# shift.net
KiCad netlist of a schematic drawn in EAGLE
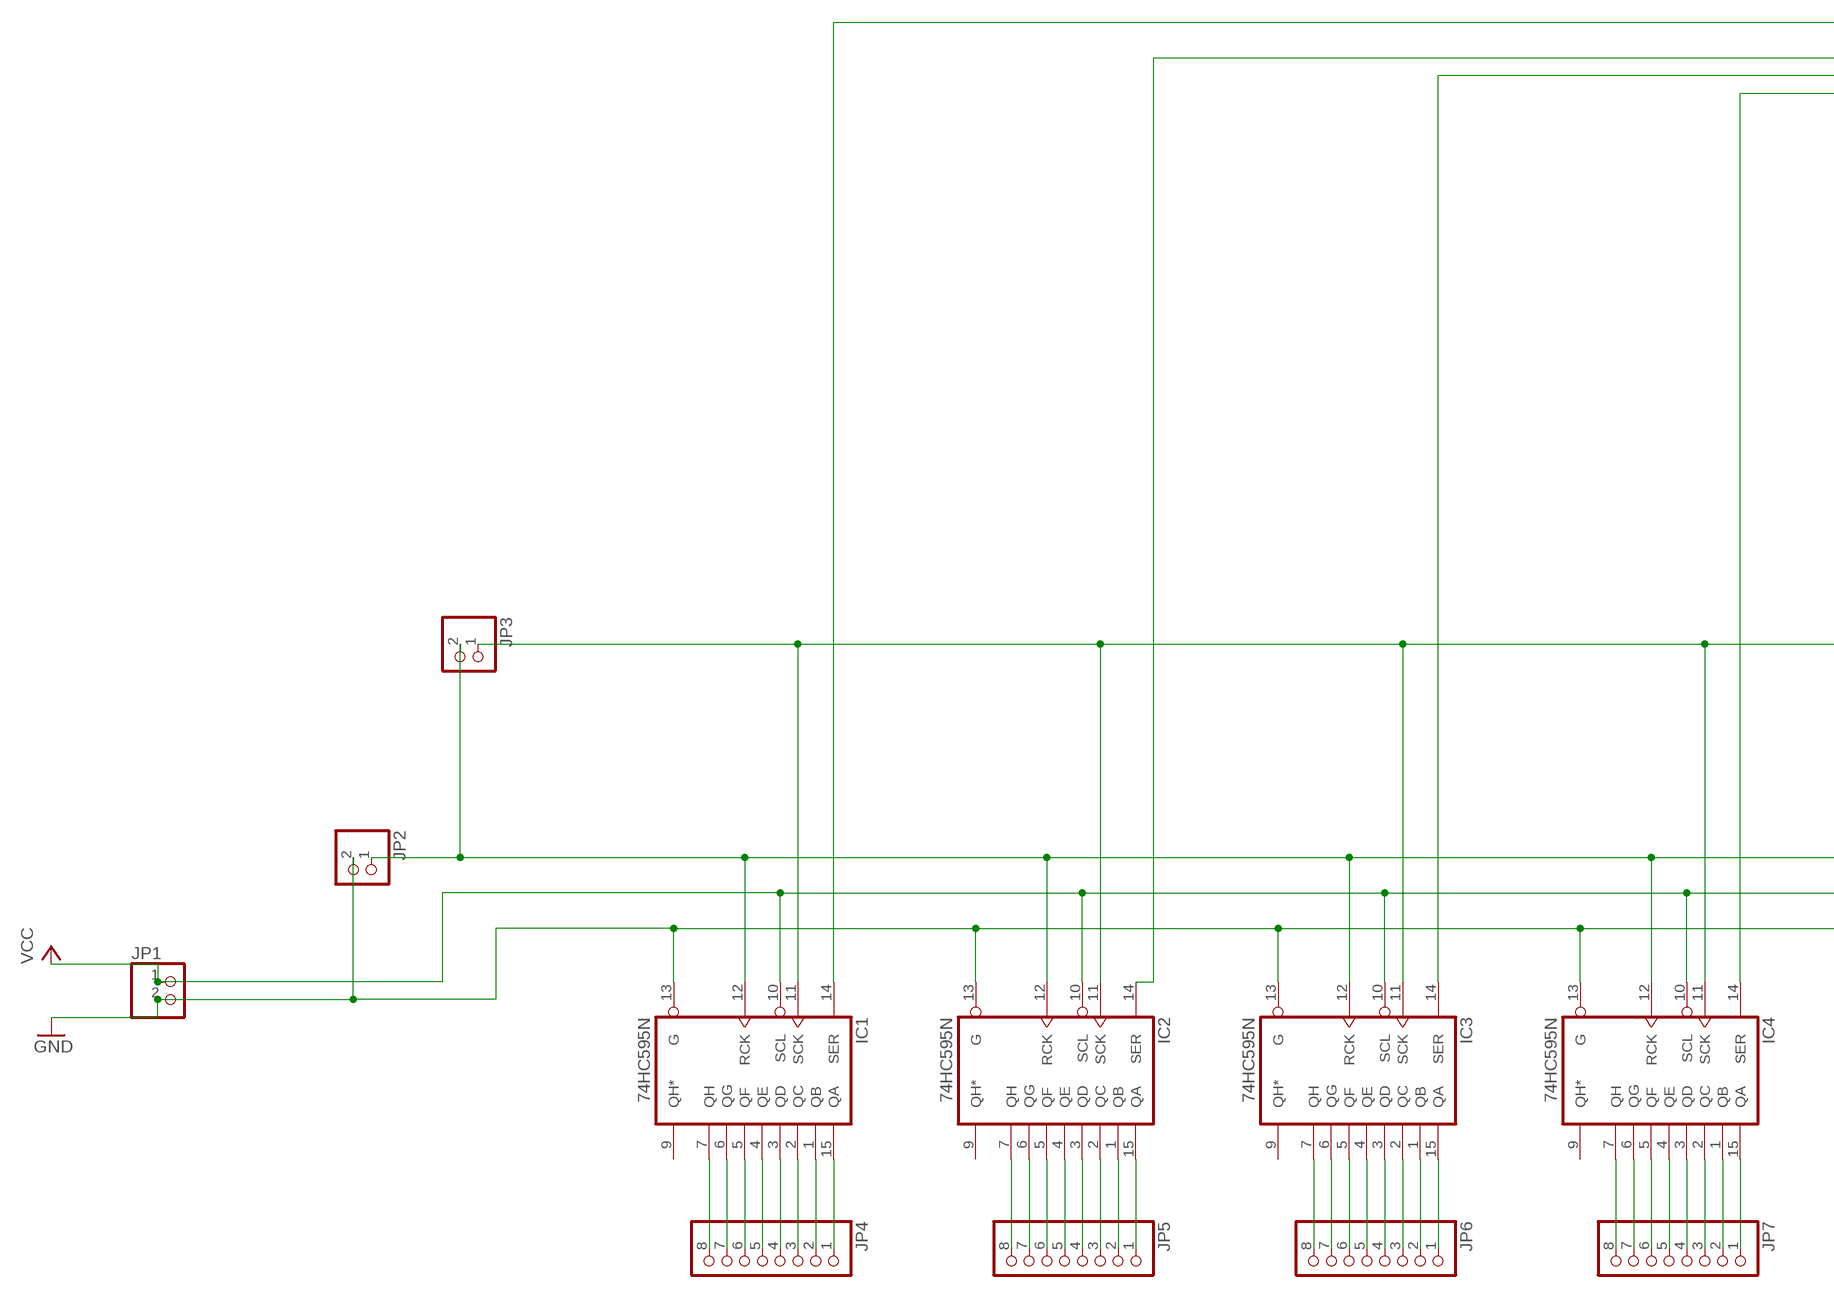
[diagram p0: schematic, sheet 1, part 1 of 2]
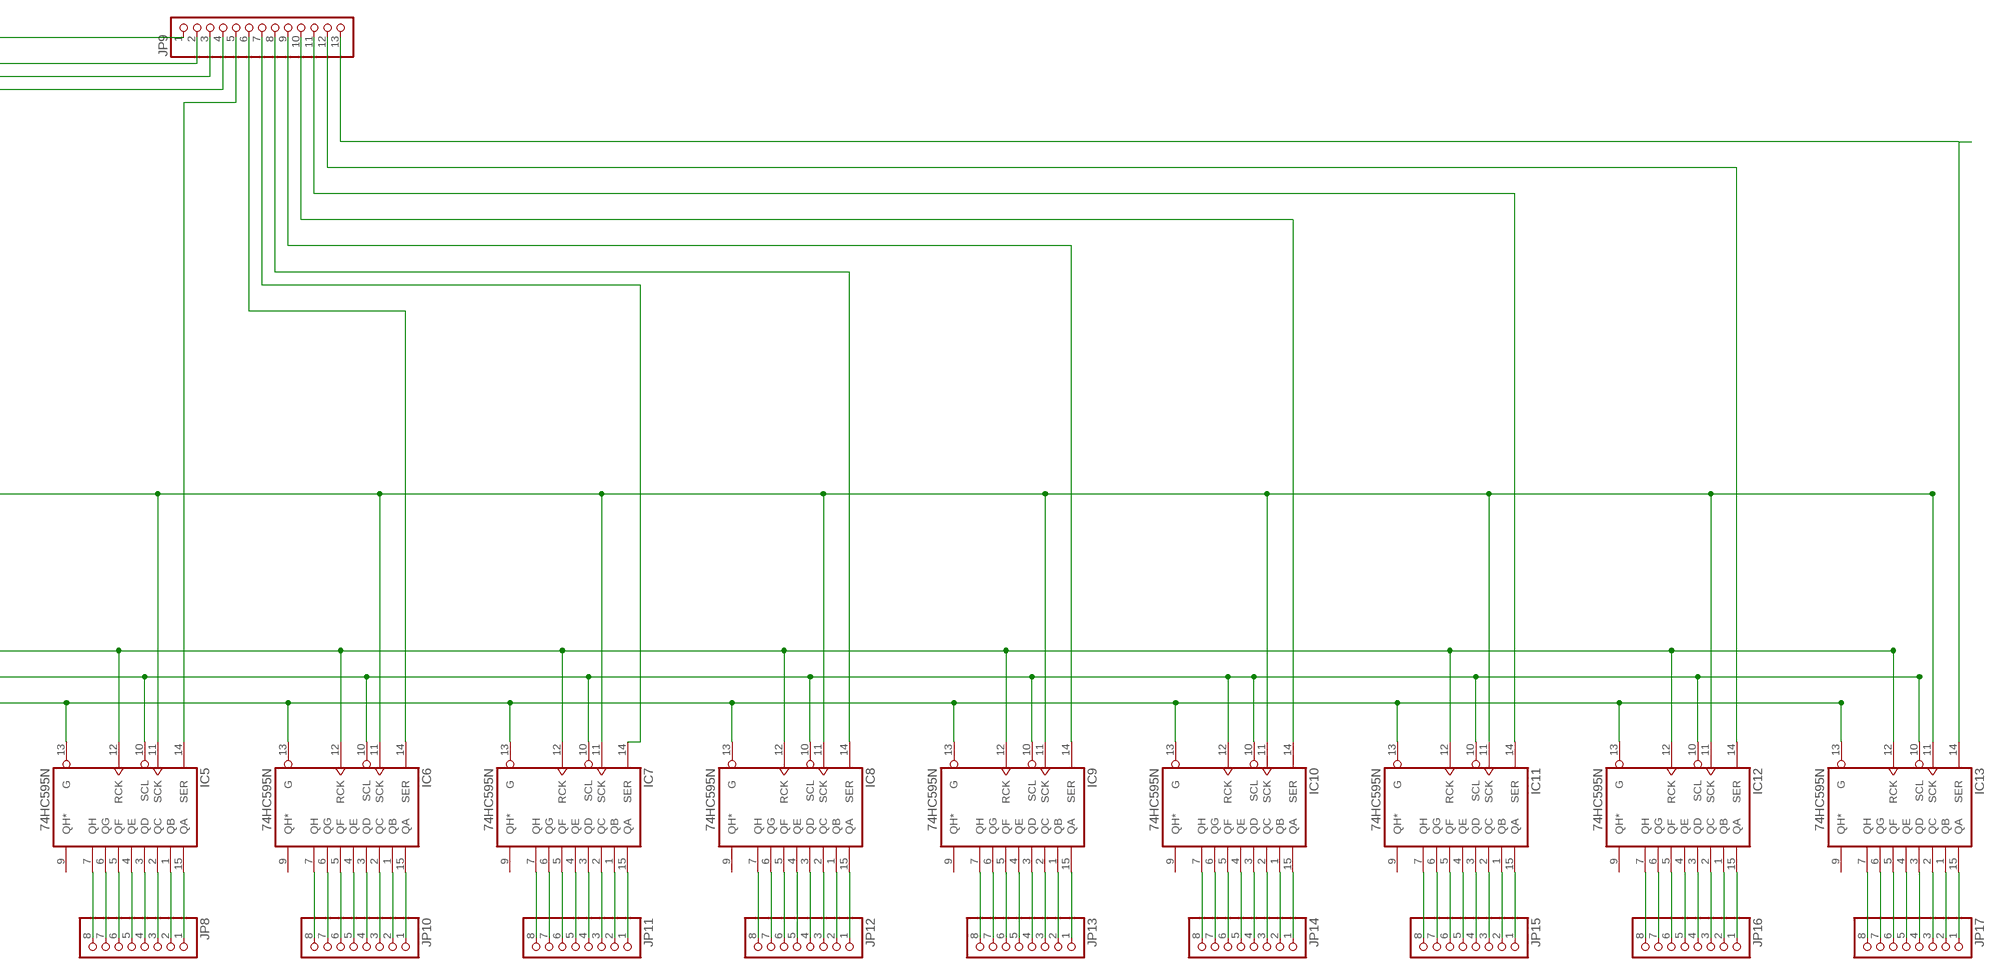
[diagram p1: schematic, sheet 1, part 2 of 2]

(export (version "E")
  (design (tool "Eeschema 10.0.6"))
  (components
    (comp (ref "IC1")
      (value "74HC595N")
      (footprint "eagle-import:DIL16")
      (libsource (lib "eagle-import") (part "74595NHC"))
    )
    (comp (ref "IC2")
      (value "74HC595N")
      (footprint "eagle-import:DIL16")
      (libsource (lib "eagle-import") (part "74595NHC"))
    )
    (comp (ref "IC3")
      (value "74HC595N")
      (footprint "eagle-import:DIL16")
      (libsource (lib "eagle-import") (part "74595NHC"))
    )
    (comp (ref "IC4")
      (value "74HC595N")
      (footprint "eagle-import:DIL16")
      (libsource (lib "eagle-import") (part "74595NHC"))
    )
    (comp (ref "IC5")
      (value "74HC595N")
      (footprint "eagle-import:DIL16")
      (libsource (lib "eagle-import") (part "74595NHC"))
    )
    (comp (ref "IC6")
      (value "74HC595N")
      (footprint "eagle-import:DIL16")
      (libsource (lib "eagle-import") (part "74595NHC"))
    )
    (comp (ref "IC7")
      (value "74HC595N")
      (footprint "eagle-import:DIL16")
      (libsource (lib "eagle-import") (part "74595NHC"))
    )
    (comp (ref "IC8")
      (value "74HC595N")
      (footprint "eagle-import:DIL16")
      (libsource (lib "eagle-import") (part "74595NHC"))
    )
    (comp (ref "IC9")
      (value "74HC595N")
      (footprint "eagle-import:DIL16")
      (libsource (lib "eagle-import") (part "74595NHC"))
    )
    (comp (ref "IC10")
      (value "74HC595N")
      (footprint "eagle-import:DIL16")
      (libsource (lib "eagle-import") (part "74595NHC"))
    )
    (comp (ref "IC11")
      (value "74HC595N")
      (footprint "eagle-import:DIL16")
      (libsource (lib "eagle-import") (part "74595NHC"))
    )
    (comp (ref "IC12")
      (value "74HC595N")
      (footprint "eagle-import:DIL16")
      (libsource (lib "eagle-import") (part "74595NHC"))
    )
    (comp (ref "IC13")
      (value "74HC595N")
      (footprint "eagle-import:DIL16")
      (libsource (lib "eagle-import") (part "74595NHC"))
    )
    (comp (ref "JP1")
      (value "PINHD-1X2")
      (footprint "eagle-import:1X02")
      (libsource (lib "eagle-import") (part "PINHD-1X2"))
    )
    (comp (ref "JP2")
      (value "PINHD-1X2")
      (footprint "eagle-import:1X02")
      (libsource (lib "eagle-import") (part "PINHD-1X2"))
    )
    (comp (ref "JP3")
      (value "PINHD-1X2")
      (footprint "eagle-import:1X02")
      (libsource (lib "eagle-import") (part "PINHD-1X2"))
    )
    (comp (ref "JP4")
      (value "PINHD-1X8")
      (footprint "eagle-import:1X08")
      (libsource (lib "eagle-import") (part "PINHD-1X8"))
    )
    (comp (ref "JP5")
      (value "PINHD-1X8")
      (footprint "eagle-import:1X08")
      (libsource (lib "eagle-import") (part "PINHD-1X8"))
    )
    (comp (ref "JP6")
      (value "PINHD-1X8")
      (footprint "eagle-import:1X08")
      (libsource (lib "eagle-import") (part "PINHD-1X8"))
    )
    (comp (ref "JP7")
      (value "PINHD-1X8")
      (footprint "eagle-import:1X08")
      (libsource (lib "eagle-import") (part "PINHD-1X8"))
    )
    (comp (ref "JP8")
      (value "PINHD-1X8")
      (footprint "eagle-import:1X08")
      (libsource (lib "eagle-import") (part "PINHD-1X8"))
    )
    (comp (ref "JP9")
      (value "PINHD-1X13")
      (footprint "eagle-import:1X13")
      (libsource (lib "eagle-import") (part "PINHD-1X13"))
    )
    (comp (ref "JP10")
      (value "PINHD-1X8")
      (footprint "eagle-import:1X08")
      (libsource (lib "eagle-import") (part "PINHD-1X8"))
    )
    (comp (ref "JP11")
      (value "PINHD-1X8")
      (footprint "eagle-import:1X08")
      (libsource (lib "eagle-import") (part "PINHD-1X8"))
    )
    (comp (ref "JP12")
      (value "PINHD-1X8")
      (footprint "eagle-import:1X08")
      (libsource (lib "eagle-import") (part "PINHD-1X8"))
    )
    (comp (ref "JP13")
      (value "PINHD-1X8")
      (footprint "eagle-import:1X08")
      (libsource (lib "eagle-import") (part "PINHD-1X8"))
    )
    (comp (ref "JP14")
      (value "PINHD-1X8")
      (footprint "eagle-import:1X08")
      (libsource (lib "eagle-import") (part "PINHD-1X8"))
    )
    (comp (ref "JP15")
      (value "PINHD-1X8")
      (footprint "eagle-import:1X08")
      (libsource (lib "eagle-import") (part "PINHD-1X8"))
    )
    (comp (ref "JP16")
      (value "PINHD-1X8")
      (footprint "eagle-import:1X08")
      (libsource (lib "eagle-import") (part "PINHD-1X8"))
    )
    (comp (ref "JP17")
      (value "PINHD-1X8")
      (footprint "eagle-import:1X08")
      (libsource (lib "eagle-import") (part "PINHD-1X8"))
    )
  )
  (nets
    (net (code "1") (name "GND") (class "Default")
      (node (ref "IC1") (pin "13") (pinfunction "G_13") (pintype "input"))
      (node (ref "IC10") (pin "13") (pinfunction "G_13") (pintype "input"))
      (node (ref "IC11") (pin "13") (pinfunction "G_13") (pintype "input"))
      (node (ref "IC12") (pin "13") (pinfunction "G_13") (pintype "input"))
      (node (ref "IC13") (pin "13") (pinfunction "G_13") (pintype "input"))
      (node (ref "IC2") (pin "13") (pinfunction "G_13") (pintype "input"))
      (node (ref "IC3") (pin "13") (pinfunction "G_13") (pintype "input"))
      (node (ref "IC4") (pin "13") (pinfunction "G_13") (pintype "input"))
      (node (ref "IC5") (pin "13") (pinfunction "G_13") (pintype "input"))
      (node (ref "IC6") (pin "13") (pinfunction "G_13") (pintype "input"))
      (node (ref "IC7") (pin "13") (pinfunction "G_13") (pintype "input"))
      (node (ref "IC8") (pin "13") (pinfunction "G_13") (pintype "input"))
      (node (ref "IC9") (pin "13") (pinfunction "G_13") (pintype "input"))
      (node (ref "JP1") (pin "2") (pinfunction "2_2") (pintype "passive"))
      (node (ref "JP2") (pin "2") (pinfunction "2_2") (pintype "passive"))
    )
    (net (code "2") (name "Net-(IC1A-QA)") (class "Default")
      (node (ref "IC1") (pin "15") (pinfunction "QA_15") (pintype "tri_state"))
      (node (ref "JP4") (pin "1") (pinfunction "1_1") (pintype "passive"))
    )
    (net (code "3") (name "Net-(IC1A-QB)") (class "Default")
      (node (ref "IC1") (pin "1") (pinfunction "QB_1") (pintype "tri_state"))
      (node (ref "JP4") (pin "2") (pinfunction "2_2") (pintype "passive"))
    )
    (net (code "4") (name "Net-(IC1A-QC)") (class "Default")
      (node (ref "IC1") (pin "2") (pinfunction "QC_2") (pintype "tri_state"))
      (node (ref "JP4") (pin "3") (pinfunction "3_3") (pintype "passive"))
    )
    (net (code "5") (name "Net-(IC1A-QD)") (class "Default")
      (node (ref "IC1") (pin "3") (pinfunction "QD_3") (pintype "tri_state"))
      (node (ref "JP4") (pin "4") (pinfunction "4_4") (pintype "passive"))
    )
    (net (code "6") (name "Net-(IC1A-QE)") (class "Default")
      (node (ref "IC1") (pin "4") (pinfunction "QE_4") (pintype "tri_state"))
      (node (ref "JP4") (pin "5") (pinfunction "5_5") (pintype "passive"))
    )
    (net (code "7") (name "Net-(IC1A-QF)") (class "Default")
      (node (ref "IC1") (pin "5") (pinfunction "QF_5") (pintype "tri_state"))
      (node (ref "JP4") (pin "6") (pinfunction "6_6") (pintype "passive"))
    )
    (net (code "8") (name "Net-(IC1A-QG)") (class "Default")
      (node (ref "IC1") (pin "6") (pinfunction "QG_6") (pintype "tri_state"))
      (node (ref "JP4") (pin "7") (pinfunction "7_7") (pintype "passive"))
    )
    (net (code "9") (name "Net-(IC1A-QH)") (class "Default")
      (node (ref "IC1") (pin "7") (pinfunction "QH_7") (pintype "tri_state"))
      (node (ref "JP4") (pin "8") (pinfunction "8_8") (pintype "passive"))
    )
    (net (code "10") (name "Net-(IC1A-SER)") (class "Default")
      (node (ref "IC1") (pin "14") (pinfunction "SER_14") (pintype "input"))
      (node (ref "JP9") (pin "1") (pinfunction "1_1") (pintype "passive"))
    )
    (net (code "11") (name "Net-(IC2A-QA)") (class "Default")
      (node (ref "IC2") (pin "15") (pinfunction "QA_15") (pintype "tri_state"))
      (node (ref "JP5") (pin "1") (pinfunction "1_1") (pintype "passive"))
    )
    (net (code "12") (name "Net-(IC2A-QB)") (class "Default")
      (node (ref "IC2") (pin "1") (pinfunction "QB_1") (pintype "tri_state"))
      (node (ref "JP5") (pin "2") (pinfunction "2_2") (pintype "passive"))
    )
    (net (code "13") (name "Net-(IC2A-QC)") (class "Default")
      (node (ref "IC2") (pin "2") (pinfunction "QC_2") (pintype "tri_state"))
      (node (ref "JP5") (pin "3") (pinfunction "3_3") (pintype "passive"))
    )
    (net (code "14") (name "Net-(IC2A-QD)") (class "Default")
      (node (ref "IC2") (pin "3") (pinfunction "QD_3") (pintype "tri_state"))
      (node (ref "JP5") (pin "4") (pinfunction "4_4") (pintype "passive"))
    )
    (net (code "15") (name "Net-(IC2A-QE)") (class "Default")
      (node (ref "IC2") (pin "4") (pinfunction "QE_4") (pintype "tri_state"))
      (node (ref "JP5") (pin "5") (pinfunction "5_5") (pintype "passive"))
    )
    (net (code "16") (name "Net-(IC2A-QF)") (class "Default")
      (node (ref "IC2") (pin "5") (pinfunction "QF_5") (pintype "tri_state"))
      (node (ref "JP5") (pin "6") (pinfunction "6_6") (pintype "passive"))
    )
    (net (code "17") (name "Net-(IC2A-QG)") (class "Default")
      (node (ref "IC2") (pin "6") (pinfunction "QG_6") (pintype "tri_state"))
      (node (ref "JP5") (pin "7") (pinfunction "7_7") (pintype "passive"))
    )
    (net (code "18") (name "Net-(IC2A-QH)") (class "Default")
      (node (ref "IC2") (pin "7") (pinfunction "QH_7") (pintype "tri_state"))
      (node (ref "JP5") (pin "8") (pinfunction "8_8") (pintype "passive"))
    )
    (net (code "19") (name "Net-(IC2A-SER)") (class "Default")
      (node (ref "IC2") (pin "14") (pinfunction "SER_14") (pintype "input"))
      (node (ref "JP9") (pin "2") (pinfunction "2_2") (pintype "passive"))
    )
    (net (code "20") (name "Net-(IC3A-QA)") (class "Default")
      (node (ref "IC3") (pin "15") (pinfunction "QA_15") (pintype "tri_state"))
      (node (ref "JP6") (pin "1") (pinfunction "1_1") (pintype "passive"))
    )
    (net (code "21") (name "Net-(IC3A-QB)") (class "Default")
      (node (ref "IC3") (pin "1") (pinfunction "QB_1") (pintype "tri_state"))
      (node (ref "JP6") (pin "2") (pinfunction "2_2") (pintype "passive"))
    )
    (net (code "22") (name "Net-(IC3A-QC)") (class "Default")
      (node (ref "IC3") (pin "2") (pinfunction "QC_2") (pintype "tri_state"))
      (node (ref "JP6") (pin "3") (pinfunction "3_3") (pintype "passive"))
    )
    (net (code "23") (name "Net-(IC3A-QD)") (class "Default")
      (node (ref "IC3") (pin "3") (pinfunction "QD_3") (pintype "tri_state"))
      (node (ref "JP6") (pin "4") (pinfunction "4_4") (pintype "passive"))
    )
    (net (code "24") (name "Net-(IC3A-QE)") (class "Default")
      (node (ref "IC3") (pin "4") (pinfunction "QE_4") (pintype "tri_state"))
      (node (ref "JP6") (pin "5") (pinfunction "5_5") (pintype "passive"))
    )
    (net (code "25") (name "Net-(IC3A-QF)") (class "Default")
      (node (ref "IC3") (pin "5") (pinfunction "QF_5") (pintype "tri_state"))
      (node (ref "JP6") (pin "6") (pinfunction "6_6") (pintype "passive"))
    )
    (net (code "26") (name "Net-(IC3A-QG)") (class "Default")
      (node (ref "IC3") (pin "6") (pinfunction "QG_6") (pintype "tri_state"))
      (node (ref "JP6") (pin "7") (pinfunction "7_7") (pintype "passive"))
    )
    (net (code "27") (name "Net-(IC3A-QH)") (class "Default")
      (node (ref "IC3") (pin "7") (pinfunction "QH_7") (pintype "tri_state"))
      (node (ref "JP6") (pin "8") (pinfunction "8_8") (pintype "passive"))
    )
    (net (code "28") (name "Net-(IC3A-SER)") (class "Default")
      (node (ref "IC3") (pin "14") (pinfunction "SER_14") (pintype "input"))
      (node (ref "JP9") (pin "3") (pinfunction "3_3") (pintype "passive"))
    )
    (net (code "29") (name "Net-(IC4A-QA)") (class "Default")
      (node (ref "IC4") (pin "15") (pinfunction "QA_15") (pintype "tri_state"))
      (node (ref "JP7") (pin "1") (pinfunction "1_1") (pintype "passive"))
    )
    (net (code "30") (name "Net-(IC4A-QB)") (class "Default")
      (node (ref "IC4") (pin "1") (pinfunction "QB_1") (pintype "tri_state"))
      (node (ref "JP7") (pin "2") (pinfunction "2_2") (pintype "passive"))
    )
    (net (code "31") (name "Net-(IC4A-QC)") (class "Default")
      (node (ref "IC4") (pin "2") (pinfunction "QC_2") (pintype "tri_state"))
      (node (ref "JP7") (pin "3") (pinfunction "3_3") (pintype "passive"))
    )
    (net (code "32") (name "Net-(IC4A-QD)") (class "Default")
      (node (ref "IC4") (pin "3") (pinfunction "QD_3") (pintype "tri_state"))
      (node (ref "JP7") (pin "4") (pinfunction "4_4") (pintype "passive"))
    )
    (net (code "33") (name "Net-(IC4A-QE)") (class "Default")
      (node (ref "IC4") (pin "4") (pinfunction "QE_4") (pintype "tri_state"))
      (node (ref "JP7") (pin "5") (pinfunction "5_5") (pintype "passive"))
    )
    (net (code "34") (name "Net-(IC4A-QF)") (class "Default")
      (node (ref "IC4") (pin "5") (pinfunction "QF_5") (pintype "tri_state"))
      (node (ref "JP7") (pin "6") (pinfunction "6_6") (pintype "passive"))
    )
    (net (code "35") (name "Net-(IC4A-QG)") (class "Default")
      (node (ref "IC4") (pin "6") (pinfunction "QG_6") (pintype "tri_state"))
      (node (ref "JP7") (pin "7") (pinfunction "7_7") (pintype "passive"))
    )
    (net (code "36") (name "Net-(IC4A-QH)") (class "Default")
      (node (ref "IC4") (pin "7") (pinfunction "QH_7") (pintype "tri_state"))
      (node (ref "JP7") (pin "8") (pinfunction "8_8") (pintype "passive"))
    )
    (net (code "37") (name "Net-(IC4A-SER)") (class "Default")
      (node (ref "IC4") (pin "14") (pinfunction "SER_14") (pintype "input"))
      (node (ref "JP9") (pin "4") (pinfunction "4_4") (pintype "passive"))
    )
    (net (code "38") (name "Net-(IC5A-QA)") (class "Default")
      (node (ref "IC5") (pin "15") (pinfunction "QA_15") (pintype "tri_state"))
      (node (ref "JP8") (pin "1") (pinfunction "1_1") (pintype "passive"))
    )
    (net (code "39") (name "Net-(IC5A-QB)") (class "Default")
      (node (ref "IC5") (pin "1") (pinfunction "QB_1") (pintype "tri_state"))
      (node (ref "JP8") (pin "2") (pinfunction "2_2") (pintype "passive"))
    )
    (net (code "40") (name "Net-(IC5A-QC)") (class "Default")
      (node (ref "IC5") (pin "2") (pinfunction "QC_2") (pintype "tri_state"))
      (node (ref "JP8") (pin "3") (pinfunction "3_3") (pintype "passive"))
    )
    (net (code "41") (name "Net-(IC5A-QD)") (class "Default")
      (node (ref "IC5") (pin "3") (pinfunction "QD_3") (pintype "tri_state"))
      (node (ref "JP8") (pin "4") (pinfunction "4_4") (pintype "passive"))
    )
    (net (code "42") (name "Net-(IC5A-QE)") (class "Default")
      (node (ref "IC5") (pin "4") (pinfunction "QE_4") (pintype "tri_state"))
      (node (ref "JP8") (pin "5") (pinfunction "5_5") (pintype "passive"))
    )
    (net (code "43") (name "Net-(IC5A-QF)") (class "Default")
      (node (ref "IC5") (pin "5") (pinfunction "QF_5") (pintype "tri_state"))
      (node (ref "JP8") (pin "6") (pinfunction "6_6") (pintype "passive"))
    )
    (net (code "44") (name "Net-(IC5A-QG)") (class "Default")
      (node (ref "IC5") (pin "6") (pinfunction "QG_6") (pintype "tri_state"))
      (node (ref "JP8") (pin "7") (pinfunction "7_7") (pintype "passive"))
    )
    (net (code "45") (name "Net-(IC5A-QH)") (class "Default")
      (node (ref "IC5") (pin "7") (pinfunction "QH_7") (pintype "tri_state"))
      (node (ref "JP8") (pin "8") (pinfunction "8_8") (pintype "passive"))
    )
    (net (code "46") (name "Net-(IC5A-SER)") (class "Default")
      (node (ref "IC5") (pin "14") (pinfunction "SER_14") (pintype "input"))
      (node (ref "JP9") (pin "5") (pinfunction "5_5") (pintype "passive"))
    )
    (net (code "47") (name "Net-(IC6A-QA)") (class "Default")
      (node (ref "IC6") (pin "15") (pinfunction "QA_15") (pintype "tri_state"))
      (node (ref "JP10") (pin "1") (pinfunction "1_1") (pintype "passive"))
    )
    (net (code "48") (name "Net-(IC6A-QB)") (class "Default")
      (node (ref "IC6") (pin "1") (pinfunction "QB_1") (pintype "tri_state"))
      (node (ref "JP10") (pin "2") (pinfunction "2_2") (pintype "passive"))
    )
    (net (code "49") (name "Net-(IC6A-QC)") (class "Default")
      (node (ref "IC6") (pin "2") (pinfunction "QC_2") (pintype "tri_state"))
      (node (ref "JP10") (pin "3") (pinfunction "3_3") (pintype "passive"))
    )
    (net (code "50") (name "Net-(IC6A-QD)") (class "Default")
      (node (ref "IC6") (pin "3") (pinfunction "QD_3") (pintype "tri_state"))
      (node (ref "JP10") (pin "4") (pinfunction "4_4") (pintype "passive"))
    )
    (net (code "51") (name "Net-(IC6A-QE)") (class "Default")
      (node (ref "IC6") (pin "4") (pinfunction "QE_4") (pintype "tri_state"))
      (node (ref "JP10") (pin "5") (pinfunction "5_5") (pintype "passive"))
    )
    (net (code "52") (name "Net-(IC6A-QF)") (class "Default")
      (node (ref "IC6") (pin "5") (pinfunction "QF_5") (pintype "tri_state"))
      (node (ref "JP10") (pin "6") (pinfunction "6_6") (pintype "passive"))
    )
    (net (code "53") (name "Net-(IC6A-QG)") (class "Default")
      (node (ref "IC6") (pin "6") (pinfunction "QG_6") (pintype "tri_state"))
      (node (ref "JP10") (pin "7") (pinfunction "7_7") (pintype "passive"))
    )
    (net (code "54") (name "Net-(IC6A-QH)") (class "Default")
      (node (ref "IC6") (pin "7") (pinfunction "QH_7") (pintype "tri_state"))
      (node (ref "JP10") (pin "8") (pinfunction "8_8") (pintype "passive"))
    )
    (net (code "55") (name "Net-(IC6A-SER)") (class "Default")
      (node (ref "IC6") (pin "14") (pinfunction "SER_14") (pintype "input"))
      (node (ref "JP9") (pin "6") (pinfunction "6_6") (pintype "passive"))
    )
    (net (code "56") (name "Net-(IC7A-QA)") (class "Default")
      (node (ref "IC7") (pin "15") (pinfunction "QA_15") (pintype "tri_state"))
      (node (ref "JP11") (pin "1") (pinfunction "1_1") (pintype "passive"))
    )
    (net (code "57") (name "Net-(IC7A-QB)") (class "Default")
      (node (ref "IC7") (pin "1") (pinfunction "QB_1") (pintype "tri_state"))
      (node (ref "JP11") (pin "2") (pinfunction "2_2") (pintype "passive"))
    )
    (net (code "58") (name "Net-(IC7A-QC)") (class "Default")
      (node (ref "IC7") (pin "2") (pinfunction "QC_2") (pintype "tri_state"))
      (node (ref "JP11") (pin "3") (pinfunction "3_3") (pintype "passive"))
    )
    (net (code "59") (name "Net-(IC7A-QD)") (class "Default")
      (node (ref "IC7") (pin "3") (pinfunction "QD_3") (pintype "tri_state"))
      (node (ref "JP11") (pin "4") (pinfunction "4_4") (pintype "passive"))
    )
    (net (code "60") (name "Net-(IC7A-QE)") (class "Default")
      (node (ref "IC7") (pin "4") (pinfunction "QE_4") (pintype "tri_state"))
      (node (ref "JP11") (pin "5") (pinfunction "5_5") (pintype "passive"))
    )
    (net (code "61") (name "Net-(IC7A-QF)") (class "Default")
      (node (ref "IC7") (pin "5") (pinfunction "QF_5") (pintype "tri_state"))
      (node (ref "JP11") (pin "6") (pinfunction "6_6") (pintype "passive"))
    )
    (net (code "62") (name "Net-(IC7A-QG)") (class "Default")
      (node (ref "IC7") (pin "6") (pinfunction "QG_6") (pintype "tri_state"))
      (node (ref "JP11") (pin "7") (pinfunction "7_7") (pintype "passive"))
    )
    (net (code "63") (name "Net-(IC7A-QH)") (class "Default")
      (node (ref "IC7") (pin "7") (pinfunction "QH_7") (pintype "tri_state"))
      (node (ref "JP11") (pin "8") (pinfunction "8_8") (pintype "passive"))
    )
    (net (code "64") (name "Net-(IC7A-SER)") (class "Default")
      (node (ref "IC7") (pin "14") (pinfunction "SER_14") (pintype "input"))
      (node (ref "JP9") (pin "7") (pinfunction "7_7") (pintype "passive"))
    )
    (net (code "65") (name "Net-(IC8A-QA)") (class "Default")
      (node (ref "IC8") (pin "15") (pinfunction "QA_15") (pintype "tri_state"))
      (node (ref "JP12") (pin "1") (pinfunction "1_1") (pintype "passive"))
    )
    (net (code "66") (name "Net-(IC8A-QB)") (class "Default")
      (node (ref "IC8") (pin "1") (pinfunction "QB_1") (pintype "tri_state"))
      (node (ref "JP12") (pin "2") (pinfunction "2_2") (pintype "passive"))
    )
    (net (code "67") (name "Net-(IC8A-QC)") (class "Default")
      (node (ref "IC8") (pin "2") (pinfunction "QC_2") (pintype "tri_state"))
      (node (ref "JP12") (pin "3") (pinfunction "3_3") (pintype "passive"))
    )
    (net (code "68") (name "Net-(IC8A-QD)") (class "Default")
      (node (ref "IC8") (pin "3") (pinfunction "QD_3") (pintype "tri_state"))
      (node (ref "JP12") (pin "4") (pinfunction "4_4") (pintype "passive"))
    )
    (net (code "69") (name "Net-(IC8A-QE)") (class "Default")
      (node (ref "IC8") (pin "4") (pinfunction "QE_4") (pintype "tri_state"))
      (node (ref "JP12") (pin "5") (pinfunction "5_5") (pintype "passive"))
    )
    (net (code "70") (name "Net-(IC8A-QF)") (class "Default")
      (node (ref "IC8") (pin "5") (pinfunction "QF_5") (pintype "tri_state"))
      (node (ref "JP12") (pin "6") (pinfunction "6_6") (pintype "passive"))
    )
    (net (code "71") (name "Net-(IC8A-QG)") (class "Default")
      (node (ref "IC8") (pin "6") (pinfunction "QG_6") (pintype "tri_state"))
      (node (ref "JP12") (pin "7") (pinfunction "7_7") (pintype "passive"))
    )
    (net (code "72") (name "Net-(IC8A-QH)") (class "Default")
      (node (ref "IC8") (pin "7") (pinfunction "QH_7") (pintype "tri_state"))
      (node (ref "JP12") (pin "8") (pinfunction "8_8") (pintype "passive"))
    )
    (net (code "73") (name "Net-(IC8A-SER)") (class "Default")
      (node (ref "IC8") (pin "14") (pinfunction "SER_14") (pintype "input"))
      (node (ref "JP9") (pin "8") (pinfunction "8_8") (pintype "passive"))
    )
    (net (code "74") (name "Net-(IC9A-QA)") (class "Default")
      (node (ref "IC9") (pin "15") (pinfunction "QA_15") (pintype "tri_state"))
      (node (ref "JP13") (pin "1") (pinfunction "1_1") (pintype "passive"))
    )
    (net (code "75") (name "Net-(IC9A-QB)") (class "Default")
      (node (ref "IC9") (pin "1") (pinfunction "QB_1") (pintype "tri_state"))
      (node (ref "JP13") (pin "2") (pinfunction "2_2") (pintype "passive"))
    )
    (net (code "76") (name "Net-(IC9A-QC)") (class "Default")
      (node (ref "IC9") (pin "2") (pinfunction "QC_2") (pintype "tri_state"))
      (node (ref "JP13") (pin "3") (pinfunction "3_3") (pintype "passive"))
    )
    (net (code "77") (name "Net-(IC9A-QD)") (class "Default")
      (node (ref "IC9") (pin "3") (pinfunction "QD_3") (pintype "tri_state"))
      (node (ref "JP13") (pin "4") (pinfunction "4_4") (pintype "passive"))
    )
    (net (code "78") (name "Net-(IC9A-QE)") (class "Default")
      (node (ref "IC9") (pin "4") (pinfunction "QE_4") (pintype "tri_state"))
      (node (ref "JP13") (pin "5") (pinfunction "5_5") (pintype "passive"))
    )
    (net (code "79") (name "Net-(IC9A-QF)") (class "Default")
      (node (ref "IC9") (pin "5") (pinfunction "QF_5") (pintype "tri_state"))
      (node (ref "JP13") (pin "6") (pinfunction "6_6") (pintype "passive"))
    )
    (net (code "80") (name "Net-(IC9A-QG)") (class "Default")
      (node (ref "IC9") (pin "6") (pinfunction "QG_6") (pintype "tri_state"))
      (node (ref "JP13") (pin "7") (pinfunction "7_7") (pintype "passive"))
    )
    (net (code "81") (name "Net-(IC9A-QH)") (class "Default")
      (node (ref "IC9") (pin "7") (pinfunction "QH_7") (pintype "tri_state"))
      (node (ref "JP13") (pin "8") (pinfunction "8_8") (pintype "passive"))
    )
    (net (code "82") (name "Net-(IC9A-SER)") (class "Default")
      (node (ref "IC9") (pin "14") (pinfunction "SER_14") (pintype "input"))
      (node (ref "JP9") (pin "9") (pinfunction "9_9") (pintype "passive"))
    )
    (net (code "83") (name "Net-(IC10A-QA)") (class "Default")
      (node (ref "IC10") (pin "15") (pinfunction "QA_15") (pintype "tri_state"))
      (node (ref "JP14") (pin "1") (pinfunction "1_1") (pintype "passive"))
    )
    (net (code "84") (name "Net-(IC10A-QB)") (class "Default")
      (node (ref "IC10") (pin "1") (pinfunction "QB_1") (pintype "tri_state"))
      (node (ref "JP14") (pin "2") (pinfunction "2_2") (pintype "passive"))
    )
    (net (code "85") (name "Net-(IC10A-QC)") (class "Default")
      (node (ref "IC10") (pin "2") (pinfunction "QC_2") (pintype "tri_state"))
      (node (ref "JP14") (pin "3") (pinfunction "3_3") (pintype "passive"))
    )
    (net (code "86") (name "Net-(IC10A-QD)") (class "Default")
      (node (ref "IC10") (pin "3") (pinfunction "QD_3") (pintype "tri_state"))
      (node (ref "JP14") (pin "4") (pinfunction "4_4") (pintype "passive"))
    )
    (net (code "87") (name "Net-(IC10A-QE)") (class "Default")
      (node (ref "IC10") (pin "4") (pinfunction "QE_4") (pintype "tri_state"))
      (node (ref "JP14") (pin "5") (pinfunction "5_5") (pintype "passive"))
    )
    (net (code "88") (name "Net-(IC10A-QF)") (class "Default")
      (node (ref "IC10") (pin "5") (pinfunction "QF_5") (pintype "tri_state"))
      (node (ref "JP14") (pin "6") (pinfunction "6_6") (pintype "passive"))
    )
    (net (code "89") (name "Net-(IC10A-QG)") (class "Default")
      (node (ref "IC10") (pin "6") (pinfunction "QG_6") (pintype "tri_state"))
      (node (ref "JP14") (pin "7") (pinfunction "7_7") (pintype "passive"))
    )
    (net (code "90") (name "Net-(IC10A-QH)") (class "Default")
      (node (ref "IC10") (pin "7") (pinfunction "QH_7") (pintype "tri_state"))
      (node (ref "JP14") (pin "8") (pinfunction "8_8") (pintype "passive"))
    )
    (net (code "91") (name "Net-(IC10A-SCK)") (class "Default")
      (node (ref "IC1") (pin "11") (pinfunction "SCK_11") (pintype "input"))
      (node (ref "IC10") (pin "11") (pinfunction "SCK_11") (pintype "input"))
      (node (ref "IC11") (pin "11") (pinfunction "SCK_11") (pintype "input"))
      (node (ref "IC12") (pin "11") (pinfunction "SCK_11") (pintype "input"))
      (node (ref "IC13") (pin "11") (pinfunction "SCK_11") (pintype "input"))
      (node (ref "IC2") (pin "11") (pinfunction "SCK_11") (pintype "input"))
      (node (ref "IC3") (pin "11") (pinfunction "SCK_11") (pintype "input"))
      (node (ref "IC4") (pin "11") (pinfunction "SCK_11") (pintype "input"))
      (node (ref "IC5") (pin "11") (pinfunction "SCK_11") (pintype "input"))
      (node (ref "IC6") (pin "11") (pinfunction "SCK_11") (pintype "input"))
      (node (ref "IC7") (pin "11") (pinfunction "SCK_11") (pintype "input"))
      (node (ref "IC8") (pin "11") (pinfunction "SCK_11") (pintype "input"))
      (node (ref "IC9") (pin "11") (pinfunction "SCK_11") (pintype "input"))
      (node (ref "JP3") (pin "1") (pinfunction "1_1") (pintype "passive"))
    )
    (net (code "92") (name "Net-(IC10A-SER)") (class "Default")
      (node (ref "IC10") (pin "14") (pinfunction "SER_14") (pintype "input"))
      (node (ref "JP9") (pin "10") (pinfunction "10_10") (pintype "passive"))
    )
    (net (code "93") (name "Net-(IC11A-QA)") (class "Default")
      (node (ref "IC11") (pin "15") (pinfunction "QA_15") (pintype "tri_state"))
      (node (ref "JP15") (pin "1") (pinfunction "1_1") (pintype "passive"))
    )
    (net (code "94") (name "Net-(IC11A-QB)") (class "Default")
      (node (ref "IC11") (pin "1") (pinfunction "QB_1") (pintype "tri_state"))
      (node (ref "JP15") (pin "2") (pinfunction "2_2") (pintype "passive"))
    )
    (net (code "95") (name "Net-(IC11A-QC)") (class "Default")
      (node (ref "IC11") (pin "2") (pinfunction "QC_2") (pintype "tri_state"))
      (node (ref "JP15") (pin "3") (pinfunction "3_3") (pintype "passive"))
    )
    (net (code "96") (name "Net-(IC11A-QD)") (class "Default")
      (node (ref "IC11") (pin "3") (pinfunction "QD_3") (pintype "tri_state"))
      (node (ref "JP15") (pin "4") (pinfunction "4_4") (pintype "passive"))
    )
    (net (code "97") (name "Net-(IC11A-QE)") (class "Default")
      (node (ref "IC11") (pin "4") (pinfunction "QE_4") (pintype "tri_state"))
      (node (ref "JP15") (pin "5") (pinfunction "5_5") (pintype "passive"))
    )
    (net (code "98") (name "Net-(IC11A-QF)") (class "Default")
      (node (ref "IC11") (pin "5") (pinfunction "QF_5") (pintype "tri_state"))
      (node (ref "JP15") (pin "6") (pinfunction "6_6") (pintype "passive"))
    )
    (net (code "99") (name "Net-(IC11A-QG)") (class "Default")
      (node (ref "IC11") (pin "6") (pinfunction "QG_6") (pintype "tri_state"))
      (node (ref "JP15") (pin "7") (pinfunction "7_7") (pintype "passive"))
    )
    (net (code "100") (name "Net-(IC11A-QH)") (class "Default")
      (node (ref "IC11") (pin "7") (pinfunction "QH_7") (pintype "tri_state"))
      (node (ref "JP15") (pin "8") (pinfunction "8_8") (pintype "passive"))
    )
    (net (code "101") (name "Net-(IC11A-RCK)") (class "Default")
      (node (ref "IC1") (pin "12") (pinfunction "RCK_12") (pintype "input"))
      (node (ref "IC11") (pin "12") (pinfunction "RCK_12") (pintype "input"))
      (node (ref "IC12") (pin "12") (pinfunction "RCK_12") (pintype "input"))
      (node (ref "IC13") (pin "12") (pinfunction "RCK_12") (pintype "input"))
      (node (ref "IC2") (pin "12") (pinfunction "RCK_12") (pintype "input"))
      (node (ref "IC3") (pin "12") (pinfunction "RCK_12") (pintype "input"))
      (node (ref "IC4") (pin "12") (pinfunction "RCK_12") (pintype "input"))
      (node (ref "IC5") (pin "12") (pinfunction "RCK_12") (pintype "input"))
      (node (ref "IC6") (pin "12") (pinfunction "RCK_12") (pintype "input"))
      (node (ref "IC7") (pin "12") (pinfunction "RCK_12") (pintype "input"))
      (node (ref "IC8") (pin "12") (pinfunction "RCK_12") (pintype "input"))
      (node (ref "IC9") (pin "12") (pinfunction "RCK_12") (pintype "input"))
      (node (ref "JP2") (pin "1") (pinfunction "1_1") (pintype "passive"))
      (node (ref "JP3") (pin "2") (pinfunction "2_2") (pintype "passive"))
    )
    (net (code "102") (name "Net-(IC11A-SER)") (class "Default")
      (node (ref "IC11") (pin "14") (pinfunction "SER_14") (pintype "input"))
      (node (ref "JP9") (pin "11") (pinfunction "11_11") (pintype "passive"))
    )
    (net (code "103") (name "Net-(IC12A-QA)") (class "Default")
      (node (ref "IC12") (pin "15") (pinfunction "QA_15") (pintype "tri_state"))
      (node (ref "JP16") (pin "1") (pinfunction "1_1") (pintype "passive"))
    )
    (net (code "104") (name "Net-(IC12A-QB)") (class "Default")
      (node (ref "IC12") (pin "1") (pinfunction "QB_1") (pintype "tri_state"))
      (node (ref "JP16") (pin "2") (pinfunction "2_2") (pintype "passive"))
    )
    (net (code "105") (name "Net-(IC12A-QC)") (class "Default")
      (node (ref "IC12") (pin "2") (pinfunction "QC_2") (pintype "tri_state"))
      (node (ref "JP16") (pin "3") (pinfunction "3_3") (pintype "passive"))
    )
    (net (code "106") (name "Net-(IC12A-QD)") (class "Default")
      (node (ref "IC12") (pin "3") (pinfunction "QD_3") (pintype "tri_state"))
      (node (ref "JP16") (pin "4") (pinfunction "4_4") (pintype "passive"))
    )
    (net (code "107") (name "Net-(IC12A-QE)") (class "Default")
      (node (ref "IC12") (pin "4") (pinfunction "QE_4") (pintype "tri_state"))
      (node (ref "JP16") (pin "5") (pinfunction "5_5") (pintype "passive"))
    )
    (net (code "108") (name "Net-(IC12A-QF)") (class "Default")
      (node (ref "IC12") (pin "5") (pinfunction "QF_5") (pintype "tri_state"))
      (node (ref "JP16") (pin "6") (pinfunction "6_6") (pintype "passive"))
    )
    (net (code "109") (name "Net-(IC12A-QG)") (class "Default")
      (node (ref "IC12") (pin "6") (pinfunction "QG_6") (pintype "tri_state"))
      (node (ref "JP16") (pin "7") (pinfunction "7_7") (pintype "passive"))
    )
    (net (code "110") (name "Net-(IC12A-QH)") (class "Default")
      (node (ref "IC12") (pin "7") (pinfunction "QH_7") (pintype "tri_state"))
      (node (ref "JP16") (pin "8") (pinfunction "8_8") (pintype "passive"))
    )
    (net (code "111") (name "Net-(IC12A-SER)") (class "Default")
      (node (ref "IC12") (pin "14") (pinfunction "SER_14") (pintype "input"))
      (node (ref "JP9") (pin "12") (pinfunction "12_12") (pintype "passive"))
    )
    (net (code "112") (name "Net-(IC13A-QA)") (class "Default")
      (node (ref "IC13") (pin "15") (pinfunction "QA_15") (pintype "tri_state"))
      (node (ref "JP17") (pin "1") (pinfunction "1_1") (pintype "passive"))
    )
    (net (code "113") (name "Net-(IC13A-QB)") (class "Default")
      (node (ref "IC13") (pin "1") (pinfunction "QB_1") (pintype "tri_state"))
      (node (ref "JP17") (pin "2") (pinfunction "2_2") (pintype "passive"))
    )
    (net (code "114") (name "Net-(IC13A-QC)") (class "Default")
      (node (ref "IC13") (pin "2") (pinfunction "QC_2") (pintype "tri_state"))
      (node (ref "JP17") (pin "3") (pinfunction "3_3") (pintype "passive"))
    )
    (net (code "115") (name "Net-(IC13A-QD)") (class "Default")
      (node (ref "IC13") (pin "3") (pinfunction "QD_3") (pintype "tri_state"))
      (node (ref "JP17") (pin "4") (pinfunction "4_4") (pintype "passive"))
    )
    (net (code "116") (name "Net-(IC13A-QE)") (class "Default")
      (node (ref "IC13") (pin "4") (pinfunction "QE_4") (pintype "tri_state"))
      (node (ref "JP17") (pin "5") (pinfunction "5_5") (pintype "passive"))
    )
    (net (code "117") (name "Net-(IC13A-QF)") (class "Default")
      (node (ref "IC13") (pin "5") (pinfunction "QF_5") (pintype "tri_state"))
      (node (ref "JP17") (pin "6") (pinfunction "6_6") (pintype "passive"))
    )
    (net (code "118") (name "Net-(IC13A-QG)") (class "Default")
      (node (ref "IC13") (pin "6") (pinfunction "QG_6") (pintype "tri_state"))
      (node (ref "JP17") (pin "7") (pinfunction "7_7") (pintype "passive"))
    )
    (net (code "119") (name "Net-(IC13A-QH)") (class "Default")
      (node (ref "IC13") (pin "7") (pinfunction "QH_7") (pintype "tri_state"))
      (node (ref "JP17") (pin "8") (pinfunction "8_8") (pintype "passive"))
    )
    (net (code "120") (name "Net-(IC13A-SER)") (class "Default")
      (node (ref "IC13") (pin "14") (pinfunction "SER_14") (pintype "input"))
      (node (ref "JP9") (pin "13") (pinfunction "13_13") (pintype "passive"))
    )
    (net (code "121") (name "VCC") (class "Default")
      (node (ref "IC1") (pin "10") (pinfunction "SCL_10") (pintype "input"))
      (node (ref "IC10") (pin "10") (pinfunction "SCL_10") (pintype "input"))
      (node (ref "IC10") (pin "12") (pinfunction "RCK_12") (pintype "input"))
      (node (ref "IC11") (pin "10") (pinfunction "SCL_10") (pintype "input"))
      (node (ref "IC12") (pin "10") (pinfunction "SCL_10") (pintype "input"))
      (node (ref "IC13") (pin "10") (pinfunction "SCL_10") (pintype "input"))
      (node (ref "IC2") (pin "10") (pinfunction "SCL_10") (pintype "input"))
      (node (ref "IC3") (pin "10") (pinfunction "SCL_10") (pintype "input"))
      (node (ref "IC4") (pin "10") (pinfunction "SCL_10") (pintype "input"))
      (node (ref "IC5") (pin "10") (pinfunction "SCL_10") (pintype "input"))
      (node (ref "IC6") (pin "10") (pinfunction "SCL_10") (pintype "input"))
      (node (ref "IC7") (pin "10") (pinfunction "SCL_10") (pintype "input"))
      (node (ref "IC8") (pin "10") (pinfunction "SCL_10") (pintype "input"))
      (node (ref "IC9") (pin "10") (pinfunction "SCL_10") (pintype "input"))
      (node (ref "JP1") (pin "1") (pinfunction "1_1") (pintype "passive"))
    )
    (net (code "122") (name "unconnected-(IC1A-QH*-Pad9)") (class "Default")
      (node (ref "IC1") (pin "9") (pinfunction "QH*_9") (pintype "tri_state"))
    )
    (net (code "123") (name "unconnected-(IC2A-QH*-Pad9)") (class "Default")
      (node (ref "IC2") (pin "9") (pinfunction "QH*_9") (pintype "tri_state"))
    )
    (net (code "124") (name "unconnected-(IC3A-QH*-Pad9)") (class "Default")
      (node (ref "IC3") (pin "9") (pinfunction "QH*_9") (pintype "tri_state"))
    )
    (net (code "125") (name "unconnected-(IC4A-QH*-Pad9)") (class "Default")
      (node (ref "IC4") (pin "9") (pinfunction "QH*_9") (pintype "tri_state"))
    )
    (net (code "126") (name "unconnected-(IC5A-QH*-Pad9)") (class "Default")
      (node (ref "IC5") (pin "9") (pinfunction "QH*_9") (pintype "tri_state"))
    )
    (net (code "127") (name "unconnected-(IC6A-QH*-Pad9)") (class "Default")
      (node (ref "IC6") (pin "9") (pinfunction "QH*_9") (pintype "tri_state"))
    )
    (net (code "128") (name "unconnected-(IC7A-QH*-Pad9)") (class "Default")
      (node (ref "IC7") (pin "9") (pinfunction "QH*_9") (pintype "tri_state"))
    )
    (net (code "129") (name "unconnected-(IC8A-QH*-Pad9)") (class "Default")
      (node (ref "IC8") (pin "9") (pinfunction "QH*_9") (pintype "tri_state"))
    )
    (net (code "130") (name "unconnected-(IC9A-QH*-Pad9)") (class "Default")
      (node (ref "IC9") (pin "9") (pinfunction "QH*_9") (pintype "tri_state"))
    )
    (net (code "131") (name "unconnected-(IC10A-QH*-Pad9)") (class "Default")
      (node (ref "IC10") (pin "9") (pinfunction "QH*_9") (pintype "tri_state"))
    )
    (net (code "132") (name "unconnected-(IC11A-QH*-Pad9)") (class "Default")
      (node (ref "IC11") (pin "9") (pinfunction "QH*_9") (pintype "tri_state"))
    )
    (net (code "133") (name "unconnected-(IC12A-QH*-Pad9)") (class "Default")
      (node (ref "IC12") (pin "9") (pinfunction "QH*_9") (pintype "tri_state"))
    )
    (net (code "134") (name "unconnected-(IC13A-QH*-Pad9)") (class "Default")
      (node (ref "IC13") (pin "9") (pinfunction "QH*_9") (pintype "tri_state"))
    )
  )
)
